# 03_USB_TO_UART.net
KiCad netlist of a schematic drawn in Altium Designer
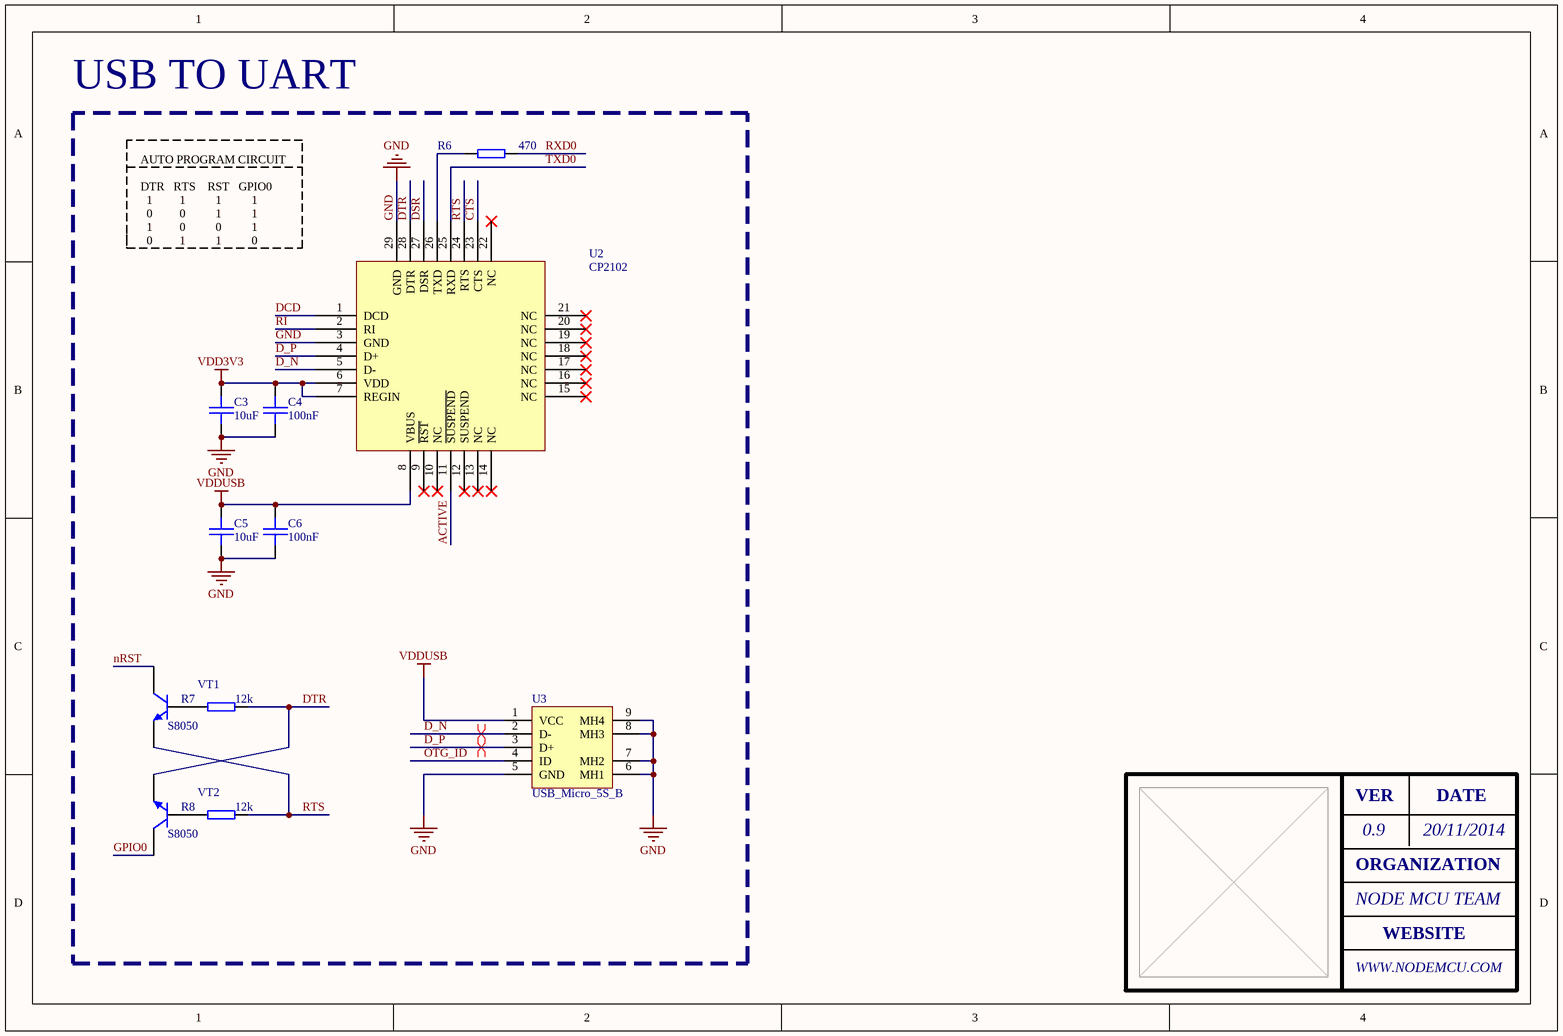
[diagram p0: 03_USB_TO_UART.SchDoc]

(export (version "E")
  (design (tool "Eeschema 10.0.6"))
  (components
    (comp (ref "C3")
      (value "10uF")
      (footprint "SMT_C_0402")
      (description "Surface mount capacitor 0402")
      (libsource (lib "cupmat") (part "SMT_C_0402"))
    )
    (comp (ref "C4")
      (value "100nF")
      (footprint "SMT_C_0402")
      (description "Surface mount capacitor 0402")
      (libsource (lib "cupmat") (part "SMT_C_0402"))
    )
    (comp (ref "C5")
      (value "10uF")
      (footprint "SMT_C_0402")
      (description "Surface mount capacitor 0402")
      (libsource (lib "cupmat") (part "SMT_C_0402"))
    )
    (comp (ref "C6")
      (value "100nF")
      (footprint "SMT_C_0402")
      (description "Surface mount capacitor 0402")
      (libsource (lib "cupmat") (part "SMT_C_0402"))
    )
    (comp (ref "R6")
      (value "470")
      (footprint "SMT_R_0402")
      (description "Surface mount resistor 0402")
      (libsource (lib "cupmat") (part "SMT_R_0402"))
    )
    (comp (ref "R7")
      (value "12k")
      (footprint "SMT_R_0402")
      (description "Surface mount resistor 0402")
      (libsource (lib "cupmat") (part "SMT_R_0402"))
    )
    (comp (ref "R8")
      (value "12k")
      (footprint "SMT_R_0402")
      (description "Surface mount resistor 0402")
      (libsource (lib "cupmat") (part "SMT_R_0402"))
    )
    (comp (ref "U2") (value "CP2102") (footprint "CP2102") (libsource (lib "cupmat") (part "CP2102")))
    (comp (ref "U3")
      (value "USB_Micro_5S_B")
      (footprint "USB_MICRO_5S_B")
      (description "USB micro female SMT with 4 fixed foot")
      (libsource (lib "cupmat") (part "USB_Micro_5S_B"))
    )
    (comp (ref "VT1")
      (value "S8050")
      (footprint "SMT_TRIODE_NPN")
      (description "Surface mount NPN transistor, package SOT-23")
      (libsource (lib "cupmat") (part "SMT_TRIODE_NPN"))
    )
    (comp (ref "VT2")
      (value "S8050")
      (footprint "SMT_TRIODE_NPN")
      (description "Surface mount NPN transistor, package SOT-23")
      (libsource (lib "cupmat") (part "SMT_TRIODE_NPN"))
    )
  )
  (nets
    (net (code "1") (name "/ACTIVE") (class "Default")
      (node (ref "U2") (pin "11") (pinfunction "~{SUSPEND}_11") (pintype "passive"))
    )
    (net (code "2") (name "/CTS") (class "Default")
      (node (ref "U2") (pin "23") (pinfunction "CTS_23") (pintype "passive"))
    )
    (net (code "3") (name "/DCD") (class "Default")
      (node (ref "U2") (pin "1") (pinfunction "DCD_1") (pintype "passive"))
    )
    (net (code "4") (name "/DSR") (class "Default")
      (node (ref "U2") (pin "27") (pinfunction "DSR_27") (pintype "passive"))
    )
    (net (code "5") (name "/DTR") (class "Default")
      (node (ref "R7") (pin "2") (pinfunction "2_2") (pintype "passive"))
      (node (ref "U2") (pin "28") (pinfunction "DTR_28") (pintype "passive"))
      (node (ref "VT2") (pin "2") (pinfunction "E_2") (pintype "passive"))
    )
    (net (code "6") (name "/D_N") (class "Default")
      (node (ref "U2") (pin "5") (pinfunction "D-_5") (pintype "passive"))
      (node (ref "U3") (pin "2") (pinfunction "D-_2") (pintype "passive"))
    )
    (net (code "7") (name "/D_P") (class "Default")
      (node (ref "U2") (pin "4") (pinfunction "D+_4") (pintype "passive"))
      (node (ref "U3") (pin "3") (pinfunction "D+_3") (pintype "passive"))
    )
    (net (code "8") (name "/GPIO0") (class "Default")
      (node (ref "VT2") (pin "3") (pinfunction "C_3") (pintype "passive"))
    )
    (net (code "9") (name "/OTG_ID") (class "Default")
      (node (ref "U3") (pin "4") (pinfunction "ID_4") (pintype "passive"))
    )
    (net (code "10") (name "/RI") (class "Default")
      (node (ref "U2") (pin "2") (pinfunction "RI_2") (pintype "passive"))
    )
    (net (code "11") (name "/RTS") (class "Default")
      (node (ref "R8") (pin "2") (pinfunction "2_2") (pintype "passive"))
      (node (ref "U2") (pin "24") (pinfunction "RTS_24") (pintype "passive"))
      (node (ref "VT1") (pin "2") (pinfunction "E_2") (pintype "passive"))
    )
    (net (code "12") (name "/RXD0") (class "Default")
      (node (ref "R6") (pin "2") (pinfunction "2_2") (pintype "passive"))
    )
    (net (code "13") (name "/TXD0") (class "Default")
      (node (ref "U2") (pin "25") (pinfunction "RXD_25") (pintype "passive"))
    )
    (net (code "14") (name "/nRST") (class "Default")
      (node (ref "VT1") (pin "3") (pinfunction "C_3") (pintype "passive"))
    )
    (net (code "15") (name "GND") (class "Default")
      (node (ref "C3") (pin "2") (pinfunction "2_2") (pintype "passive"))
      (node (ref "C4") (pin "2") (pinfunction "2_2") (pintype "passive"))
      (node (ref "C5") (pin "2") (pinfunction "2_2") (pintype "passive"))
      (node (ref "C6") (pin "2") (pinfunction "2_2") (pintype "passive"))
      (node (ref "U2") (pin "29") (pinfunction "GND_29") (pintype "passive"))
      (node (ref "U2") (pin "3") (pinfunction "GND_3") (pintype "passive"))
      (node (ref "U3") (pin "5") (pinfunction "GND_5") (pintype "passive"))
      (node (ref "U3") (pin "6") (pinfunction "MH1_6") (pintype "passive"))
      (node (ref "U3") (pin "7") (pinfunction "MH2_7") (pintype "passive"))
      (node (ref "U3") (pin "8") (pinfunction "MH3_8") (pintype "passive"))
      (node (ref "U3") (pin "9") (pinfunction "MH4_9") (pintype "passive"))
    )
    (net (code "16") (name "Net-(U2-TXD)") (class "Default")
      (node (ref "R6") (pin "1") (pinfunction "1_1") (pintype "passive"))
      (node (ref "U2") (pin "26") (pinfunction "TXD_26") (pintype "passive"))
    )
    (net (code "17") (name "Net-(VT1-B)") (class "Default")
      (node (ref "R7") (pin "1") (pinfunction "1_1") (pintype "passive"))
      (node (ref "VT1") (pin "1") (pinfunction "B_1") (pintype "passive"))
    )
    (net (code "18") (name "Net-(VT2-B)") (class "Default")
      (node (ref "R8") (pin "1") (pinfunction "1_1") (pintype "passive"))
      (node (ref "VT2") (pin "1") (pinfunction "B_1") (pintype "passive"))
    )
    (net (code "19") (name "VDD3V3") (class "Default")
      (node (ref "C3") (pin "1") (pinfunction "1_1") (pintype "passive"))
      (node (ref "C4") (pin "1") (pinfunction "1_1") (pintype "passive"))
      (node (ref "U2") (pin "6") (pinfunction "VDD_6") (pintype "passive"))
      (node (ref "U2") (pin "7") (pinfunction "REGIN_7") (pintype "passive"))
    )
    (net (code "20") (name "VDDUSB") (class "Default")
      (node (ref "C5") (pin "1") (pinfunction "1_1") (pintype "passive"))
      (node (ref "C6") (pin "1") (pinfunction "1_1") (pintype "passive"))
      (node (ref "U2") (pin "8") (pinfunction "VBUS_8") (pintype "passive"))
      (node (ref "U3") (pin "1") (pinfunction "VCC_1") (pintype "passive"))
    )
    (net (code "21") (name "unconnected-(U2-NC-Pad10)") (class "Default")
      (node (ref "U2") (pin "10") (pinfunction "NC_10") (pintype "passive+no_connect"))
    )
    (net (code "22") (name "unconnected-(U2-NC-Pad13)") (class "Default")
      (node (ref "U2") (pin "13") (pinfunction "NC_13") (pintype "passive+no_connect"))
    )
    (net (code "23") (name "unconnected-(U2-NC-Pad14)") (class "Default")
      (node (ref "U2") (pin "14") (pinfunction "NC_14") (pintype "passive+no_connect"))
    )
    (net (code "24") (name "unconnected-(U2-NC-Pad15)") (class "Default")
      (node (ref "U2") (pin "15") (pinfunction "NC_15") (pintype "passive+no_connect"))
    )
    (net (code "25") (name "unconnected-(U2-NC-Pad16)") (class "Default")
      (node (ref "U2") (pin "16") (pinfunction "NC_16") (pintype "passive+no_connect"))
    )
    (net (code "26") (name "unconnected-(U2-NC-Pad17)") (class "Default")
      (node (ref "U2") (pin "17") (pinfunction "NC_17") (pintype "passive+no_connect"))
    )
    (net (code "27") (name "unconnected-(U2-NC-Pad18)") (class "Default")
      (node (ref "U2") (pin "18") (pinfunction "NC_18") (pintype "passive+no_connect"))
    )
    (net (code "28") (name "unconnected-(U2-NC-Pad19)") (class "Default")
      (node (ref "U2") (pin "19") (pinfunction "NC_19") (pintype "passive+no_connect"))
    )
    (net (code "29") (name "unconnected-(U2-NC-Pad20)") (class "Default")
      (node (ref "U2") (pin "20") (pinfunction "NC_20") (pintype "passive+no_connect"))
    )
    (net (code "30") (name "unconnected-(U2-NC-Pad21)") (class "Default")
      (node (ref "U2") (pin "21") (pinfunction "NC_21") (pintype "passive+no_connect"))
    )
    (net (code "31") (name "unconnected-(U2-NC-Pad22)") (class "Default")
      (node (ref "U2") (pin "22") (pinfunction "NC_22") (pintype "passive+no_connect"))
    )
    (net (code "32") (name "unconnected-(U2-SUSPEND-Pad12)") (class "Default")
      (node (ref "U2") (pin "12") (pinfunction "SUSPEND_12") (pintype "passive+no_connect"))
    )
    (net (code "33") (name "unconnected-(U2-~{RST}-Pad9)") (class "Default")
      (node (ref "U2") (pin "9") (pinfunction "~{RST}_9") (pintype "passive+no_connect"))
    )
  )
)
